# HEADERS_UNO.net
KiCad netlist of a schematic drawn in Altium Designer
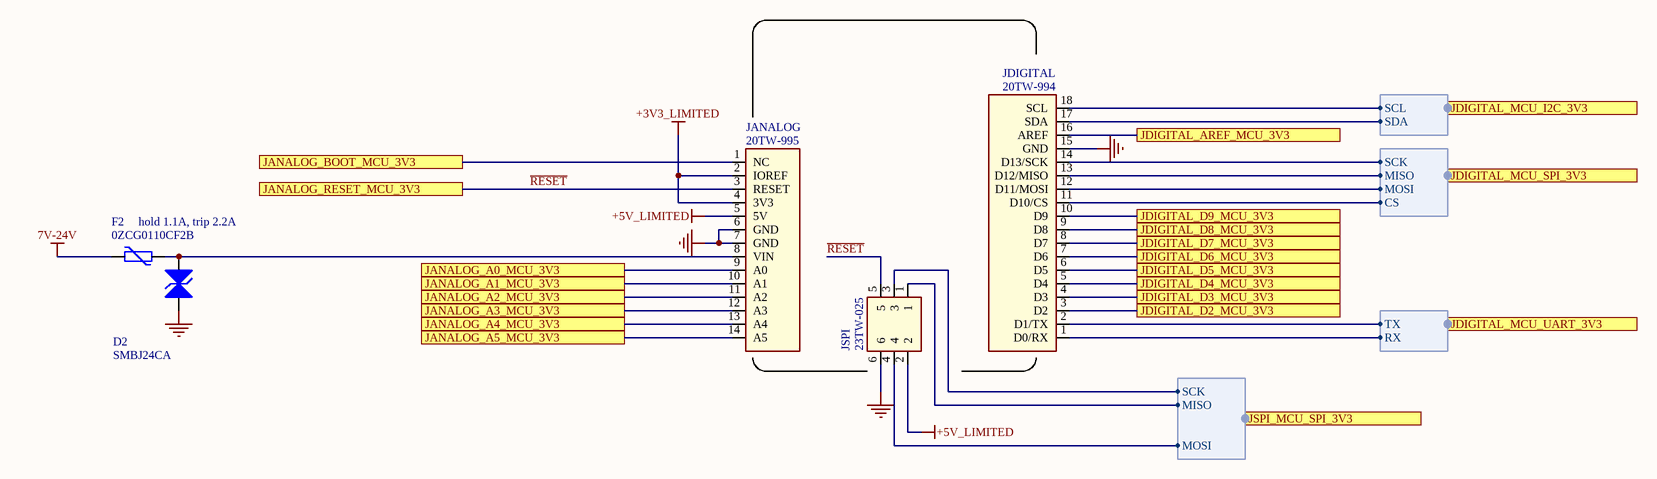
[diagram p0: HEADERS_UNO.SchDoc]

(export (version "E")
  (design (tool "Eeschema 10.0.6"))
  (components
    (comp (ref "D2")
      (value "SMBJ24CA")
      (footprint "SMB_NOPOLARITY")
      (description "TVS BIDIRECTIONAL SMD Vr 24V, Vbr min 26.7V, 600W, SMB")
      (fields (field (name "MANUFACTURER") "Littlefuse"))
      (libsource (lib "Clean") (part "Diode TVS"))
    )
    (comp (ref "F2")
      (value "0ZCG0110CF2B")
      (footprint "1812")
      (description "PTC Ihold 1.1A Itrip 2.2A 33V 1812")
      (fields (field (name "MANUFACTURER") "Bel Fuse"))
      (libsource (lib "Clean") (part "Symbol"))
    )
    (comp (ref "JANALOG")
      (value "20TW-995")
      (footprint "1X14-CUSTOM")
      (fields (field (name "MANUFACTURER") "4UCONN"))
      (libsource (lib "Clean") (part "20TW-995"))
    )
    (comp (ref "JDIGITAL")
      (value "20TW-994")
      (footprint "1X18-CUSTOM")
      (fields (field (name "MANUFACTURER") "4UCONN"))
      (libsource (lib "Clean") (part "20TW-994"))
    )
    (comp (ref "JSPI")
      (value "23TW-025")
      (footprint "23TW-025")
      (description "CONN HEADER MALE 6POS 2x3 2.54mm SMD")
      (fields (field (name "MANUFACTURER") "4UCONN"))
      (libsource (lib "Clean") (part "23TW-025"))
    )
  )
  (nets
    (net (code "5") (name "+3V3_LIMITED") (class "Default")
      (node (ref "JANALOG") (pin "2") (pinfunction "IOREF_2") (pintype "passive"))
      (node (ref "JANALOG") (pin "4") (pinfunction "3V3_4") (pintype "passive"))
    )
    (net (code "6") (name "+5V_LIMITED") (class "Default")
      (node (ref "JANALOG") (pin "5") (pinfunction "5V_5") (pintype "passive"))
      (node (ref "JSPI") (pin "2") (pinfunction "2_2") (pintype "passive"))
    )
    (net (code "7") (name "/CS") (class "Default")
      (node (ref "JDIGITAL") (pin "11") (pinfunction "D10/CS_11") (pintype "passive"))
    )
    (net (code "8") (name "/JANALOG_A0_MCU_3V3") (class "Default")
      (node (ref "JANALOG") (pin "9") (pinfunction "A0_9") (pintype "passive"))
    )
    (net (code "9") (name "/JANALOG_A1_MCU_3V3") (class "Default")
      (node (ref "JANALOG") (pin "10") (pinfunction "A1_10") (pintype "passive"))
    )
    (net (code "10") (name "/JANALOG_A2_MCU_3V3") (class "Default")
      (node (ref "JANALOG") (pin "11") (pinfunction "A2_11") (pintype "passive"))
    )
    (net (code "11") (name "/JANALOG_A3_MCU_3V3") (class "Default")
      (node (ref "JANALOG") (pin "12") (pinfunction "A3_12") (pintype "passive"))
    )
    (net (code "12") (name "/JANALOG_A4_MCU_3V3") (class "Default")
      (node (ref "JANALOG") (pin "13") (pinfunction "A4_13") (pintype "passive"))
    )
    (net (code "13") (name "/JANALOG_A5_MCU_3V3") (class "Default")
      (node (ref "JANALOG") (pin "14") (pinfunction "A5_14") (pintype "passive"))
    )
    (net (code "14") (name "/JANALOG_BOOT_MCU_3V3") (class "Default")
      (node (ref "JANALOG") (pin "1") (pinfunction "NC_1") (pintype "passive"))
    )
    (net (code "15") (name "/JDIGITAL_AREF_MCU_3V3") (class "Default")
      (node (ref "JDIGITAL") (pin "16") (pinfunction "AREF_16") (pintype "passive"))
    )
    (net (code "16") (name "/JDIGITAL_D2_MCU_3V3") (class "Default")
      (node (ref "JDIGITAL") (pin "3") (pinfunction "D2_3") (pintype "passive"))
    )
    (net (code "17") (name "/JDIGITAL_D3_MCU_3V3") (class "Default")
      (node (ref "JDIGITAL") (pin "4") (pinfunction "D3_4") (pintype "passive"))
    )
    (net (code "18") (name "/JDIGITAL_D4_MCU_3V3") (class "Default")
      (node (ref "JDIGITAL") (pin "5") (pinfunction "D4_5") (pintype "passive"))
    )
    (net (code "19") (name "/JDIGITAL_D5_MCU_3V3") (class "Default")
      (node (ref "JDIGITAL") (pin "6") (pinfunction "D5_6") (pintype "passive"))
    )
    (net (code "20") (name "/JDIGITAL_D6_MCU_3V3") (class "Default")
      (node (ref "JDIGITAL") (pin "7") (pinfunction "D6_7") (pintype "passive"))
    )
    (net (code "21") (name "/JDIGITAL_D7_MCU_3V3") (class "Default")
      (node (ref "JDIGITAL") (pin "8") (pinfunction "D7_8") (pintype "passive"))
    )
    (net (code "22") (name "/JDIGITAL_D8_MCU_3V3") (class "Default")
      (node (ref "JDIGITAL") (pin "9") (pinfunction "D8_9") (pintype "passive"))
    )
    (net (code "23") (name "/JDIGITAL_D9_MCU_3V3") (class "Default")
      (node (ref "JDIGITAL") (pin "10") (pinfunction "D9_10") (pintype "passive"))
    )
    (net (code "24") (name "/RX") (class "Default")
      (node (ref "JDIGITAL") (pin "1") (pinfunction "D0/RX_1") (pintype "passive"))
    )
    (net (code "25") (name "/SCL") (class "Default")
      (node (ref "JDIGITAL") (pin "18") (pinfunction "SCL_18") (pintype "passive"))
    )
    (net (code "26") (name "/SDA") (class "Default")
      (node (ref "JDIGITAL") (pin "17") (pinfunction "SDA_17") (pintype "passive"))
    )
    (net (code "27") (name "/TX") (class "Default")
      (node (ref "JDIGITAL") (pin "2") (pinfunction "D1/TX_2") (pintype "passive"))
    )
    (net (code "32") (name "/~{RESET}") (class "Default")
      (node (ref "JANALOG") (pin "3") (pinfunction "RESET_3") (pintype "passive"))
      (node (ref "JSPI") (pin "5") (pinfunction "5_5") (pintype "passive"))
    )
    (net (code "33") (name "7V-24V") (class "Default")
      (node (ref "F2") (pin "1") (pinfunction "1_1") (pintype "passive"))
    )
    (net (code "34") (name "GND") (class "Default")
      (node (ref "D2") (pin "1") (pinfunction "A1_1") (pintype "passive"))
      (node (ref "JANALOG") (pin "6") (pinfunction "GND_6") (pintype "passive"))
      (node (ref "JANALOG") (pin "7") (pinfunction "GND_7") (pintype "passive"))
      (node (ref "JDIGITAL") (pin "15") (pinfunction "GND_15") (pintype "passive"))
      (node (ref "JSPI") (pin "6") (pinfunction "6_6") (pintype "passive"))
    )
    (net (code "35") (name "Net-(D2-A2)") (class "Default")
      (node (ref "D2") (pin "2") (pinfunction "A2_2") (pintype "passive"))
      (node (ref "F2") (pin "2") (pinfunction "2_2") (pintype "passive"))
      (node (ref "JANALOG") (pin "8") (pinfunction "VIN_8") (pintype "passive"))
    )
    (net (code "36") (name "unconnected-(JDIGITAL-D11{slash}MOSI-Pad12)") (class "Default")
      (node (ref "JDIGITAL") (pin "12") (pinfunction "D11/MOSI_12") (pintype "passive"))
    )
    (net (code "37") (name "unconnected-(JDIGITAL-D12{slash}MISO-Pad13)") (class "Default")
      (node (ref "JDIGITAL") (pin "13") (pinfunction "D12/MISO_13") (pintype "passive"))
    )
    (net (code "38") (name "unconnected-(JDIGITAL-D13{slash}SCK-Pad14)") (class "Default")
      (node (ref "JDIGITAL") (pin "14") (pinfunction "D13/SCK_14") (pintype "passive"))
    )
    (net (code "39") (name "unconnected-(JSPI-Pad1)") (class "Default")
      (node (ref "JSPI") (pin "1") (pinfunction "1_1") (pintype "passive"))
    )
    (net (code "40") (name "unconnected-(JSPI-Pad3)") (class "Default")
      (node (ref "JSPI") (pin "3") (pinfunction "3_3") (pintype "passive"))
    )
    (net (code "41") (name "unconnected-(JSPI-Pad4)") (class "Default")
      (node (ref "JSPI") (pin "4") (pinfunction "4_4") (pintype "passive"))
    )
  )
)
